# RVPOVP.net
KiCad netlist of a schematic drawn in Altium Designer
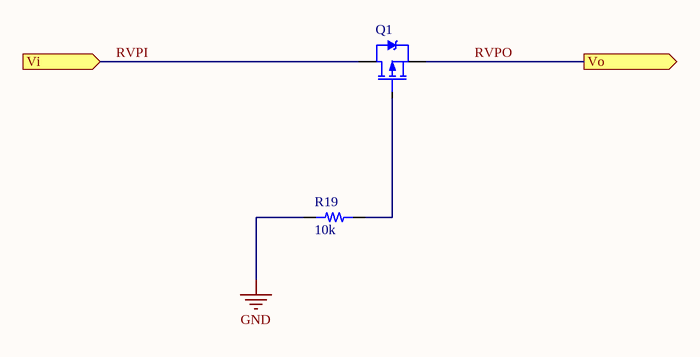
[diagram p0: RVPOVP.SchDoc]

(export (version "E")
  (design (tool "Eeschema 10.0.6"))
  (components
    (comp (ref "Q1")
      (value "DMP3010LK3-13")
      (footprint "DMP3010LK3-13")
      (description "P-Channel MOSFET 30V 17A TO252")
      (fields (field (name "CREATEDBY") "Kevin"))
      (libsource (lib "altlib") (part "DMP3010LK3-13"))
    )
    (comp (ref "R19")
      (value "10k")
      (footprint "RES 0603/1608")
      (fields (field (name "RESISTANCE") "10k"))
      (libsource (lib "altlib") (part "Resistor"))
    )
  )
  (nets
    (net (code "1") (name "/RVPI") (class "Default")
      (node (ref "Q1") (pin "3") (pinfunction "D_3") (pintype "passive"))
    )
    (net (code "2") (name "/RVPO") (class "Default")
      (node (ref "Q1") (pin "2") (pinfunction "S_2") (pintype "passive"))
    )
    (net (code "3") (name "GND") (class "Default")
      (node (ref "R19") (pin "1") (pinfunction "1_1") (pintype "passive"))
    )
    (net (code "4") (name "Net-(Q1-G)") (class "Default")
      (node (ref "Q1") (pin "1") (pinfunction "G_1") (pintype "passive"))
      (node (ref "R19") (pin "2") (pinfunction "2_2") (pintype "passive"))
    )
  )
)
